# ESP_Grow_Main_V2_4_3V_5V.net
KiCad netlist of a schematic drawn in Altium Designer
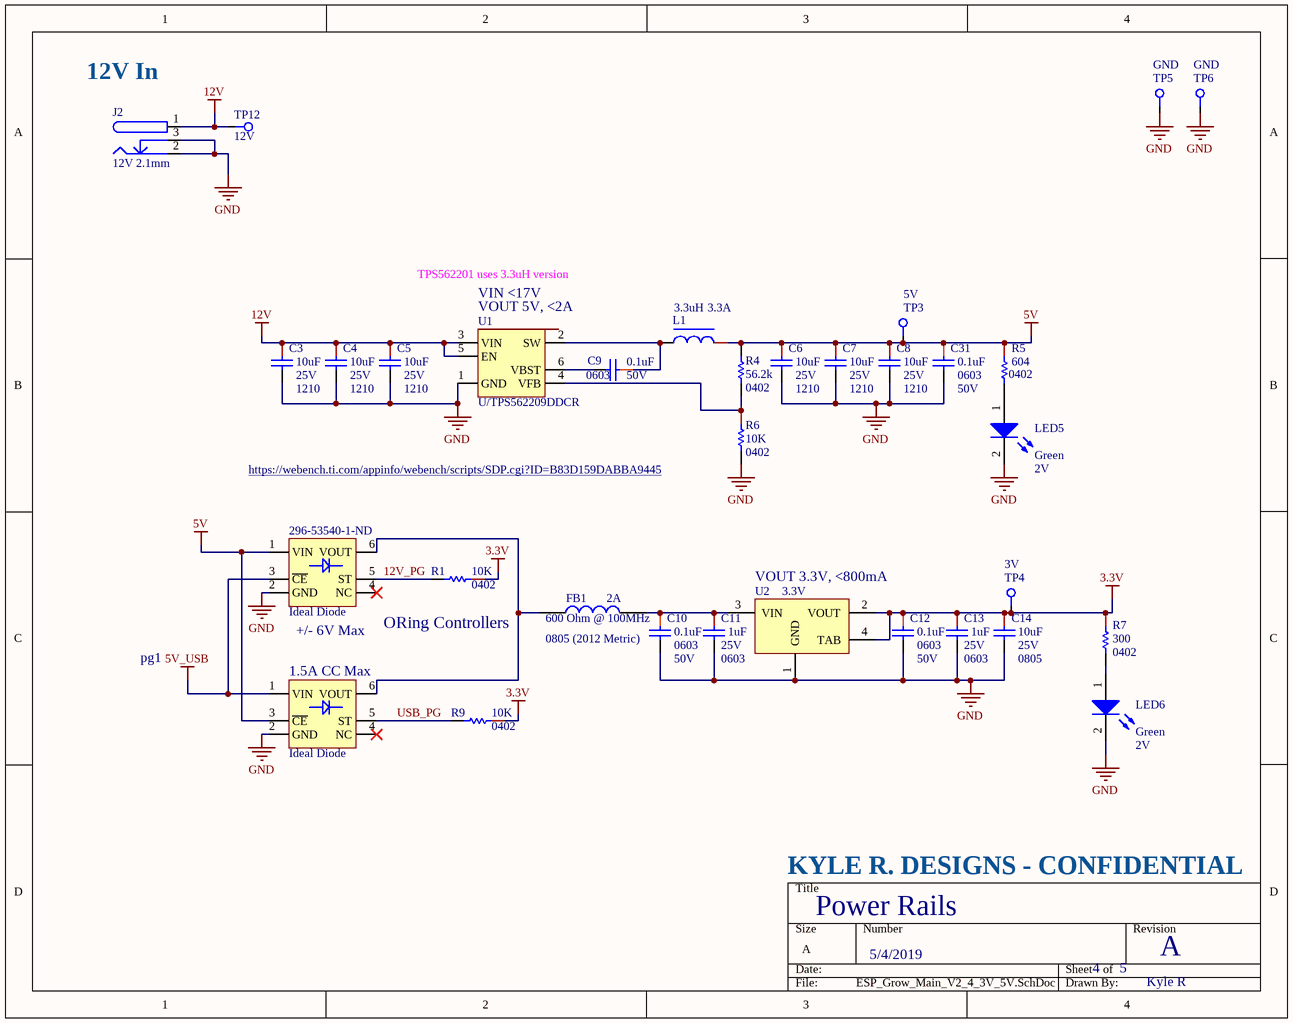
[diagram p0: ESP_Grow_Main_V2_4_3V_5V.SchDoc]

(export (version "E")
  (design (tool "Eeschema 10.0.6"))
  (components
    (comp (ref "C3")
      (value "10uF")
      (footprint "CAPC1210(3225)_N")
      (description "10uF 1210 25V")
      (fields
        (field (name "MANUFACTURER") "TDK Corporation")
        (field (name "MANUFACTURER PART NUMBER") "C3225JB1E106K250AA")
        (field (name "PACKAGE / CASE") "1210")
        (field (name "VOLTAGE RATED") "25V")
      )
      (libsource (lib "OLogic-Passive") (part "CAP CER 10UF 25V JB 1210"))
    )
    (comp (ref "C4")
      (value "10uF")
      (footprint "CAPC1210(3225)_N")
      (description "10uF 1210 25V")
      (fields
        (field (name "MANUFACTURER") "TDK Corporation")
        (field (name "MANUFACTURER PART NUMBER") "C3225JB1E106K250AA")
        (field (name "PACKAGE / CASE") "1210")
        (field (name "VOLTAGE RATED") "25V")
      )
      (libsource (lib "OLogic-Passive") (part "CAP CER 10UF 25V JB 1210"))
    )
    (comp (ref "C5")
      (value "10uF")
      (footprint "CAPC1210(3225)_N")
      (description "10uF 1210 25V")
      (fields
        (field (name "MANUFACTURER") "TDK Corporation")
        (field (name "MANUFACTURER PART NUMBER") "C3225JB1E106K250AA")
        (field (name "PACKAGE / CASE") "1210")
        (field (name "VOLTAGE RATED") "25V")
      )
      (libsource (lib "OLogic-Passive") (part "CAP CER 10UF 25V JB 1210"))
    )
    (comp (ref "C6")
      (value "10uF")
      (footprint "CAPC1210(3225)_N")
      (description "10uF 1210 25V")
      (fields
        (field (name "MANUFACTURER") "TDK Corporation")
        (field (name "MANUFACTURER PART NUMBER") "C3225JB1E106K250AA")
        (field (name "PACKAGE / CASE") "1210")
        (field (name "VOLTAGE RATED") "25V")
      )
      (libsource (lib "OLogic-Passive") (part "CAP CER 10UF 25V JB 1210"))
    )
    (comp (ref "C7")
      (value "10uF")
      (footprint "CAPC1210(3225)_N")
      (description "10uF 1210 25V")
      (fields
        (field (name "MANUFACTURER") "TDK Corporation")
        (field (name "MANUFACTURER PART NUMBER") "C3225JB1E106K250AA")
        (field (name "PACKAGE / CASE") "1210")
        (field (name "VOLTAGE RATED") "25V")
      )
      (libsource (lib "OLogic-Passive") (part "CAP CER 10UF 25V JB 1210"))
    )
    (comp (ref "C8")
      (value "10uF")
      (footprint "CAPC1210(3225)_N")
      (description "10uF 1210 25V")
      (fields
        (field (name "MANUFACTURER") "TDK Corporation")
        (field (name "MANUFACTURER PART NUMBER") "C3225JB1E106K250AA")
        (field (name "PACKAGE / CASE") "1210")
        (field (name "VOLTAGE RATED") "25V")
      )
      (libsource (lib "OLogic-Passive") (part "CAP CER 10UF 25V JB 1210"))
    )
    (comp (ref "C9")
      (value "0.1uF")
      (footprint "CAPC0603(1608)_L")
      (description "100NF 50V 0603")
      (fields
        (field (name "MANUFACTURER") "YAGEO")
        (field (name "MANUFACTURER PART NUMBER") "CC0603KRX7R9BB104")
        (field (name "CAPACITANCE") "0.1uF")
        (field (name "PACKAGE / CASE") "0603")
        (field (name "VOLTAGE - RATED") "50V")
      )
      (libsource (lib "JLCPCB_Capacitors") (part "0.1uF_0603"))
    )
    (comp (ref "C10")
      (value "0.1uF")
      (footprint "CAPC0603(1608)_L")
      (description "100NF 50V 0603")
      (fields
        (field (name "MANUFACTURER") "YAGEO")
        (field (name "MANUFACTURER PART NUMBER") "CC0603KRX7R9BB104")
        (field (name "CAPACITANCE") "0.1uF")
        (field (name "PACKAGE / CASE") "0603")
        (field (name "VOLTAGE - RATED") "50V")
      )
      (libsource (lib "JLCPCB_Capacitors") (part "0.1uF_0603"))
    )
    (comp (ref "C11")
      (value "1uF")
      (footprint "CAPC0603(1608)_N")
      (description "1uF 0603 25V")
      (fields
        (field (name "MANUFACTURER") "TDK Corporation")
        (field (name "MANUFACTURER PART NUMBER") "CGA3E1X7R1E105K080AC")
        (field (name "VOLTAGE - RATED") "25V")
        (field (name "PACKAGE / CASE") "0603")
      )
      (libsource (lib "OLogic-Passive") (part "CAP CER 1UF 25V 10% X7R 0603"))
    )
    (comp (ref "C12")
      (value "0.1uF")
      (footprint "CAPC0603(1608)_L")
      (description "100NF 50V 0603")
      (fields
        (field (name "MANUFACTURER") "YAGEO")
        (field (name "MANUFACTURER PART NUMBER") "CC0603KRX7R9BB104")
        (field (name "CAPACITANCE") "0.1uF")
        (field (name "PACKAGE / CASE") "0603")
        (field (name "VOLTAGE - RATED") "50V")
      )
      (libsource (lib "JLCPCB_Capacitors") (part "0.1uF_0603"))
    )
    (comp (ref "C13")
      (value "1uF")
      (footprint "CAPC0603(1608)_N")
      (description "1uF 0603 25V")
      (fields
        (field (name "MANUFACTURER") "TDK Corporation")
        (field (name "MANUFACTURER PART NUMBER") "CGA3E1X7R1E105K080AC")
        (field (name "VOLTAGE - RATED") "25V")
        (field (name "PACKAGE / CASE") "0603")
      )
      (libsource (lib "OLogic-Passive") (part "CAP CER 1UF 25V 10% X7R 0603"))
    )
    (comp (ref "C14")
      (value "10uF")
      (footprint "CAPC0805(2012)_L")
      (description "10UF 25V X6R 0805")
      (fields
        (field (name "MANUFACTURER") "Murata Electronics North America")
        (field (name "MANUFACTURER PART NUMBER") "GRM21BC81E106ME51L")
        (field (name "VOLTAGE - RATED") "25V")
        (field (name "PACKAGE / CASE") "0805")
      )
      (libsource (lib "OLogic-Passive") (part "CAP CER 10UF 25V X6S 0805"))
    )
    (comp (ref "C31")
      (value "0.1uF")
      (footprint "CAPC0603(1608)_L")
      (description "100NF 50V 0603")
      (fields
        (field (name "MANUFACTURER") "YAGEO")
        (field (name "MANUFACTURER PART NUMBER") "CC0603KRX7R9BB104")
        (field (name "CAPACITANCE") "0.1uF")
        (field (name "PACKAGE / CASE") "0603")
        (field (name "VOLTAGE - RATED") "50V")
      )
      (libsource (lib "JLCPCB_Capacitors") (part "0.1uF_0603"))
    )
    (comp (ref "FB1")
      (value "600 Ohm @ 100MHz")
      (footprint "RESC0805(2012)_N")
      (description "600 OHM 0805 2.0A")
      (fields
        (field (name "MANUFACTURER") "Wurth Electronics Inc")
        (field (name "MANUFACTURER PART NUMBER") "742792040")
        (field (name "CURRENT RATING") "2A")
        (field (name "PACKAGE / CASE") "0805 (2012 Metric)")
        (field (name "CREATOR") "osman")
      )
      (libsource (lib "OLogic-Passive") (part "FERRITE 600 OHM 2.0A 0805"))
    )
    (comp (ref "J2")
      (value "12V 2.1mm")
      (footprint "CONN_PWR_JACK_2.1x5.5mm")
      (description "2.1 mm barrel jack")
      (fields
        (field (name "MANUFACTURER") "CUI Inc")
        (field (name "MANUFACTURER PART NUMBER") "PJ-002A")
        (field (name "PUBLISHER") "Altium Limited")
      )
      (libsource (lib "OLogic-Connectors") (part "CONN PWR JACK 2.1"))
    )
    (comp (ref "L1")
      (value "3.3uH ±20% 3.3A 87mΩ")
      (footprint "MWSA0402S-3R3MT")
      (description "3.3uH ±20% 3.3A 87mΩ SMD,4.2x4.4x2.0mm Power Inductors RoHS")
      (fields
        (field (name "LCSC PART NUMBER") "C408336")
        (field (name "MANUFACTURER") "Sunlord")
        (field (name "INDUCTANCE") "3.3uH")
        (field (name "MAX CURRENT") "3.3A")
      )
      (libsource (lib "JLCPCB_Magnetics") (part "3.3uH"))
    )
    (comp (ref "LED5")
      (value "5V")
      (footprint "SM-LED-0603")
      (description "LED GREEN CLEAR THIN 0603 SMD")
      (fields
        (field (name "MANUFACTURER PART NUMBER") "LTST-C191KGKT")
        (field (name "COLOR") "Green")
        (field (name "MANUFACTURER") "Lite-On Inc")
        (field (name "VOLTAGE - FORWARD (VF) (TYP)") "2V")
      )
      (libsource (lib "OLogic Nexus Vault") (part "OL_LED"))
    )
    (comp (ref "LED6")
      (value "3.3V")
      (footprint "SM-LED-0603")
      (description "LED GREEN CLEAR THIN 0603 SMD")
      (fields
        (field (name "MANUFACTURER PART NUMBER") "LTST-C191KGKT")
        (field (name "COLOR") "Green")
        (field (name "MANUFACTURER") "Lite-On Inc")
        (field (name "VOLTAGE - FORWARD (VF) (TYP)") "2V")
      )
      (libsource (lib "OLogic Nexus Vault") (part "OL_LED"))
    )
    (comp (ref "R1")
      (value "0402WGF1002TCE")
      (footprint "RESC0402(1005)_N")
      (description "10KOHMS ±1% 1/10W 0402")
      (fields (field (name "RESISTANCE") "10K") (field (name "PACKAGE") "0402"))
      (libsource (lib "JLCPCB_Resistors") (part "10k_0402"))
    )
    (comp (ref "R4")
      (value "56.2K 1%")
      (footprint "RESC0402(1005)_N")
      (description "56.2K 1% 0402")
      (fields
        (field (name "MANUFACTURER") "Panasonic Electronic Components")
        (field (name "MANUFACTURER PART NUMBER") "ERJ-2RKF5622X")
        (field (name "RESISTANCE (OHMS)") "56.2k")
        (field (name "PACKAGE / CASE") "0402")
      )
      (libsource (lib "OLogic-Passive") (part "RES 56.2K OHM 1% 1/10W 0402"))
    )
    (comp (ref "R5")
      (value "604")
      (footprint "RESC0402(1005)_M")
      (description "RES 604 OHM 1% 1/10W 0402")
      (fields
        (field (name "PACKAGE (IMPERIAL)") "0402")
        (field (name "RESISTANCE") "604")
        (field (name "TOLERANCE") "1%")
        (field (name "POWER") "63mW")
      )
      (libsource (lib "OLogic Nexus Vault") (part "=Resistance"))
    )
    (comp (ref "R6")
      (value "0402WGF1002TCE")
      (footprint "RESC0402(1005)_N")
      (description "10KOHMS ±1% 1/10W 0402")
      (fields (field (name "RESISTANCE") "10K") (field (name "PACKAGE") "0402"))
      (libsource (lib "JLCPCB_Resistors") (part "10k_0402"))
    )
    (comp (ref "R7")
      (value "RES SMD 300 OHM 1% 1/10W 0402")
      (footprint "RESC0402(1005)_L")
      (description "300 Ohms ±1% 0.1W, 1/10W Chip Resistor 0402 (1005 Metric) Automotive AEC-Q200 Thick Film")
      (fields
        (field (name "PACKAGE (IMPERIAL)") "0402")
        (field (name "TOLERANCE") "1%")
        (field (name "POWER") "100mW")
        (field (name "RESISTANCE") "300")
      )
      (libsource (lib "OLogic Nexus Vault") (part "OL_Resistor"))
    )
    (comp (ref "R9")
      (value "0402WGF1002TCE")
      (footprint "RESC0402(1005)_N")
      (description "10KOHMS ±1% 1/10W 0402")
      (fields (field (name "RESISTANCE") "10K") (field (name "PACKAGE") "0402"))
      (libsource (lib "JLCPCB_Resistors") (part "10k_0402"))
    )
    (comp (ref "TP3")
      (value "5V")
      (footprint "Pogo-Testpoint")
      (description "Test Point- Current one")
      (libsource (lib "OLogic Nexus Vault") (part "TestPoint"))
    )
    (comp (ref "TP4")
      (value "3V")
      (footprint "Pogo-Testpoint")
      (description "Test Point- Current one")
      (libsource (lib "OLogic Nexus Vault") (part "TestPoint"))
    )
    (comp (ref "TP5")
      (value "GND")
      (footprint "Pogo-Testpoint")
      (description "Test Point- Current one")
      (libsource (lib "OLogic Nexus Vault") (part "TestPoint"))
    )
    (comp (ref "TP6")
      (value "GND")
      (footprint "Pogo-Testpoint")
      (description "Test Point- Current one")
      (libsource (lib "OLogic Nexus Vault") (part "TestPoint"))
    )
    (comp (ref "TP12")
      (value "12V")
      (footprint "Pogo-Testpoint")
      (description "Test Point- Current one")
      (libsource (lib "OLogic Nexus Vault") (part "TestPoint"))
    )
    (comp (ref "U1")
      (value "U/TPS562209DDCR")
      (footprint "SOT-23")
      (description "IC REG BUCK ADJ 2A TSOT23-6")
      (fields (field (name "MANUFACTURER PART NUMBER") "TPS562209DDCR"))
      (libsource (lib "Kyle_Lib_04-20-19") (part "U/TPS562209DDCR"))
    )
    (comp (ref "U2")
      (value "3.3V")
      (footprint "DSO-G3")
      (description "3.3 volt fixed regulator, 800mA")
      (libsource (lib "OLogic-Reg-Convert") (part "LD1117S33"))
    )
    (comp (ref "U14")
      (value "Ideal Diode")
      (footprint "SC-70-6")
      (description "OR Controller P-Channel 1.5A CC")
      (fields (field (name "SUPPLIER PART NUMBER 1") "296-53540-1-ND"))
      (libsource (lib "Kyle-Reg-Convert") (part "LM66100DCKT"))
    )
    (comp (ref "U15")
      (value "Ideal Diode")
      (footprint "SC-70-6")
      (description "OR Controller P-Channel 1.5A CC")
      (libsource (lib "Kyle-Reg-Convert") (part "LM66100DCKT"))
    )
  )
  (nets
    (net (code "1") (name "/12V_PG") (class "Default")
      (node (ref "R1") (pin "2") (pinfunction "2_2") (pintype "passive"))
      (node (ref "U14") (pin "5") (pinfunction "ST_5") (pintype "passive"))
    )
    (net (code "2") (name "/USB_PG") (class "Default")
      (node (ref "R9") (pin "2") (pinfunction "2_2") (pintype "passive"))
      (node (ref "U15") (pin "5") (pinfunction "ST_5") (pintype "passive"))
    )
    (net (code "3") (name "3.3V") (class "Default")
      (node (ref "C12") (pin "1") (pinfunction "1_1") (pintype "passive"))
      (node (ref "C13") (pin "1") (pinfunction "1_1") (pintype "passive"))
      (node (ref "C14") (pin "1") (pinfunction "1_1") (pintype "passive"))
      (node (ref "R1") (pin "1") (pinfunction "1_1") (pintype "passive"))
      (node (ref "R7") (pin "1") (pinfunction "1_1") (pintype "passive"))
      (node (ref "R9") (pin "1") (pinfunction "1_1") (pintype "passive"))
      (node (ref "TP4") (pin "1") (pinfunction "1_1") (pintype "passive"))
      (node (ref "U2") (pin "2") (pinfunction "VOUT_2") (pintype "power_in"))
      (node (ref "U2") (pin "4") (pinfunction "TAB_4") (pintype "power_in"))
    )
    (net (code "4") (name "5V") (class "Default")
      (node (ref "C31") (pin "1") (pinfunction "1_1") (pintype "passive"))
      (node (ref "C6") (pin "1") (pinfunction "1_1") (pintype "passive"))
      (node (ref "C7") (pin "1") (pinfunction "1_1") (pintype "passive"))
      (node (ref "C8") (pin "1") (pinfunction "1_1") (pintype "passive"))
      (node (ref "L1") (pin "1") (pinfunction "1_1") (pintype "power_in"))
      (node (ref "R4") (pin "2") (pinfunction "2_2") (pintype "passive"))
      (node (ref "R5") (pin "1") (pinfunction "1_1") (pintype "passive"))
      (node (ref "TP3") (pin "1") (pinfunction "1_1") (pintype "passive"))
      (node (ref "U14") (pin "1") (pinfunction "VIN_1") (pintype "passive"))
      (node (ref "U15") (pin "3") (pinfunction "~{CE}_3") (pintype "passive"))
    )
    (net (code "5") (name "5V_USB") (class "Default")
      (node (ref "U14") (pin "3") (pinfunction "~{CE}_3") (pintype "passive"))
      (node (ref "U15") (pin "1") (pinfunction "VIN_1") (pintype "passive"))
    )
    (net (code "6") (name "12V") (class "Default")
      (node (ref "C3") (pin "1") (pinfunction "1_1") (pintype "passive"))
      (node (ref "C4") (pin "1") (pinfunction "1_1") (pintype "passive"))
      (node (ref "C5") (pin "1") (pinfunction "1_1") (pintype "passive"))
      (node (ref "J2") (pin "1") (pinfunction "1_1") (pintype "power_in"))
      (node (ref "TP12") (pin "1") (pinfunction "1_1") (pintype "passive"))
      (node (ref "U1") (pin "3") (pinfunction "VIN_3") (pintype "power_in"))
      (node (ref "U1") (pin "5") (pinfunction "EN_5") (pintype "power_in"))
    )
    (net (code "7") (name "GND") (class "Default")
      (node (ref "C10") (pin "2") (pinfunction "2_2") (pintype "passive"))
      (node (ref "C11") (pin "2") (pinfunction "2_2") (pintype "passive"))
      (node (ref "C12") (pin "2") (pinfunction "2_2") (pintype "passive"))
      (node (ref "C13") (pin "2") (pinfunction "2_2") (pintype "passive"))
      (node (ref "C14") (pin "2") (pinfunction "2_2") (pintype "passive"))
      (node (ref "C3") (pin "2") (pinfunction "2_2") (pintype "passive"))
      (node (ref "C31") (pin "2") (pinfunction "2_2") (pintype "passive"))
      (node (ref "C4") (pin "2") (pinfunction "2_2") (pintype "passive"))
      (node (ref "C5") (pin "2") (pinfunction "2_2") (pintype "passive"))
      (node (ref "C6") (pin "2") (pinfunction "2_2") (pintype "passive"))
      (node (ref "C7") (pin "2") (pinfunction "2_2") (pintype "passive"))
      (node (ref "C8") (pin "2") (pinfunction "2_2") (pintype "passive"))
      (node (ref "J2") (pin "2") (pinfunction "2_2") (pintype "power_in"))
      (node (ref "J2") (pin "3") (pinfunction "3_3") (pintype "power_in"))
      (node (ref "LED5") (pin "2") (pinfunction "K_2") (pintype "passive"))
      (node (ref "LED6") (pin "2") (pinfunction "K_2") (pintype "passive"))
      (node (ref "R6") (pin "2") (pinfunction "2_2") (pintype "passive"))
      (node (ref "TP5") (pin "1") (pinfunction "1_1") (pintype "passive"))
      (node (ref "TP6") (pin "1") (pinfunction "1_1") (pintype "passive"))
      (node (ref "U1") (pin "1") (pinfunction "GND_1") (pintype "power_in"))
      (node (ref "U14") (pin "2") (pinfunction "GND_2") (pintype "passive"))
      (node (ref "U15") (pin "2") (pinfunction "GND_2") (pintype "passive"))
      (node (ref "U2") (pin "1") (pinfunction "GND_1") (pintype "power_in"))
    )
    (net (code "8") (name "Net-(LED5-A)") (class "Default")
      (node (ref "LED5") (pin "1") (pinfunction "A_1") (pintype "passive"))
      (node (ref "R5") (pin "2") (pinfunction "2_2") (pintype "passive"))
    )
    (net (code "9") (name "Net-(LED6-A)") (class "Default")
      (node (ref "LED6") (pin "1") (pinfunction "A_1") (pintype "passive"))
      (node (ref "R7") (pin "2") (pinfunction "2_2") (pintype "passive"))
    )
    (net (code "10") (name "Net-(U1-SW)") (class "Default")
      (node (ref "C9") (pin "1") (pinfunction "1_1") (pintype "passive"))
      (node (ref "L1") (pin "2") (pinfunction "2_2") (pintype "power_in"))
      (node (ref "U1") (pin "2") (pinfunction "SW_2") (pintype "power_in"))
    )
    (net (code "11") (name "Net-(U1-VBST)") (class "Default")
      (node (ref "C9") (pin "2") (pinfunction "2_2") (pintype "passive"))
      (node (ref "U1") (pin "6") (pinfunction "VBST_6") (pintype "power_in"))
    )
    (net (code "12") (name "Net-(U1-VFB)") (class "Default")
      (node (ref "R4") (pin "1") (pinfunction "1_1") (pintype "passive"))
      (node (ref "R6") (pin "1") (pinfunction "1_1") (pintype "passive"))
      (node (ref "U1") (pin "4") (pinfunction "VFB_4") (pintype "power_in"))
    )
    (net (code "13") (name "Net-(U2-VIN)") (class "Default")
      (node (ref "C10") (pin "1") (pinfunction "1_1") (pintype "passive"))
      (node (ref "C11") (pin "1") (pinfunction "1_1") (pintype "passive"))
      (node (ref "FB1") (pin "2") (pinfunction "2_2") (pintype "passive"))
      (node (ref "U2") (pin "3") (pinfunction "VIN_3") (pintype "power_in"))
    )
    (net (code "14") (name "Net-(U14-VOUT)") (class "Default")
      (node (ref "FB1") (pin "1") (pinfunction "1_1") (pintype "passive"))
      (node (ref "U14") (pin "6") (pinfunction "VOUT_6") (pintype "passive"))
      (node (ref "U15") (pin "6") (pinfunction "VOUT_6") (pintype "passive"))
    )
    (net (code "15") (name "unconnected-(U14-NC-Pad4)") (class "Default")
      (node (ref "U14") (pin "4") (pinfunction "NC_4") (pintype "passive+no_connect"))
    )
    (net (code "16") (name "unconnected-(U15-NC-Pad4)") (class "Default")
      (node (ref "U15") (pin "4") (pinfunction "NC_4") (pintype "passive+no_connect"))
    )
  )
)
